# Lora_Basic_Gateway__Module_V1_0_20230419.net
KiCad netlist of a schematic drawn in EAGLE
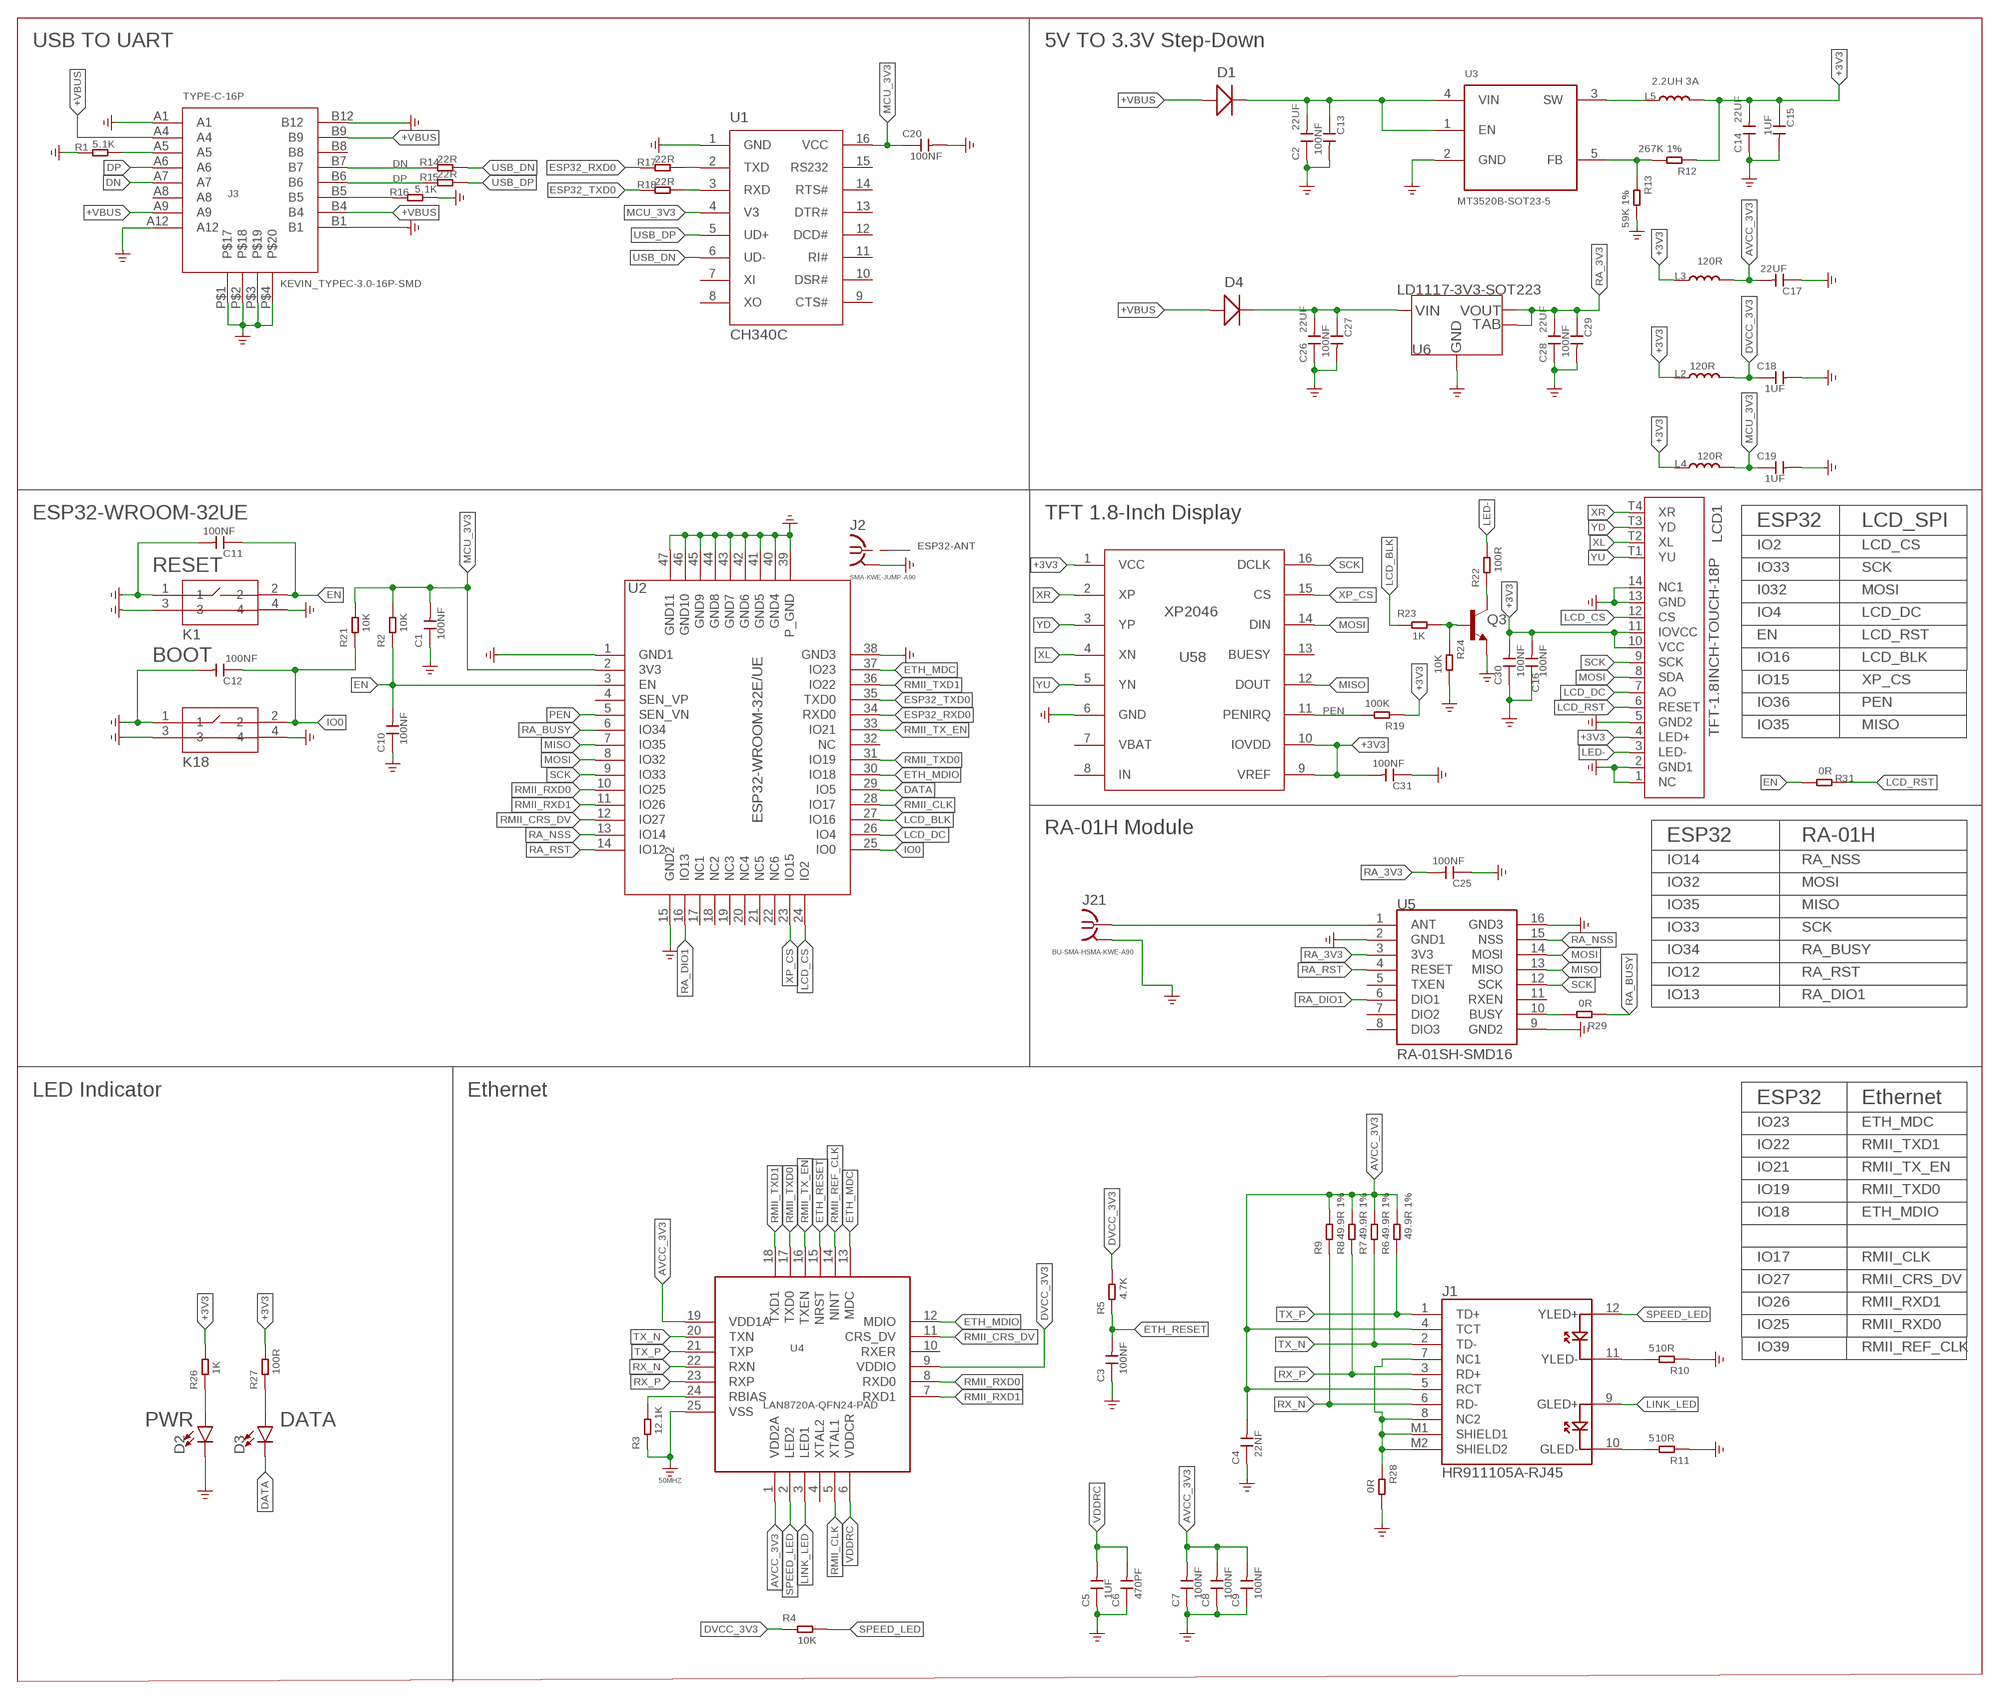
[diagram p0: schematic, sheet 1]

(export (version "E")
  (design (tool "Eeschema 10.0.6"))
  (components
    (comp (ref "C1")
      (value "100NF")
      (footprint "eagle-import:C0603")
      (libsource (lib "eagle-import") (part "C0603"))
    )
    (comp (ref "C2")
      (value "22UF")
      (footprint "eagle-import:C0805")
      (libsource (lib "eagle-import") (part "C0805"))
    )
    (comp (ref "C3")
      (value "100NF")
      (footprint "eagle-import:C0603")
      (libsource (lib "eagle-import") (part "C0603"))
    )
    (comp (ref "C4")
      (value "22NF")
      (footprint "eagle-import:C0603")
      (libsource (lib "eagle-import") (part "C0603"))
    )
    (comp (ref "C5")
      (value "1UF")
      (footprint "eagle-import:C0603")
      (libsource (lib "eagle-import") (part "C0603"))
    )
    (comp (ref "C6")
      (value "470PF")
      (footprint "eagle-import:C0603")
      (libsource (lib "eagle-import") (part "C0603"))
    )
    (comp (ref "C7")
      (value "100NF")
      (footprint "eagle-import:C0603")
      (libsource (lib "eagle-import") (part "C0603"))
    )
    (comp (ref "C8")
      (value "100NF")
      (footprint "eagle-import:C0603")
      (libsource (lib "eagle-import") (part "C0603"))
    )
    (comp (ref "C9")
      (value "100NF")
      (footprint "eagle-import:C0603")
      (libsource (lib "eagle-import") (part "C0603"))
    )
    (comp (ref "C10")
      (value "100NF")
      (footprint "eagle-import:C0603")
      (libsource (lib "eagle-import") (part "C0603"))
    )
    (comp (ref "C11")
      (value "100NF")
      (footprint "eagle-import:C0603")
      (libsource (lib "eagle-import") (part "C0603"))
    )
    (comp (ref "C12")
      (value "100NF")
      (footprint "eagle-import:C0603")
      (libsource (lib "eagle-import") (part "C0603"))
    )
    (comp (ref "C13")
      (value "100NF")
      (footprint "eagle-import:C0603")
      (libsource (lib "eagle-import") (part "C0603"))
    )
    (comp (ref "C14")
      (value "22UF")
      (footprint "eagle-import:C0805")
      (libsource (lib "eagle-import") (part "C0805"))
    )
    (comp (ref "C15")
      (value "1UF")
      (footprint "eagle-import:C0603")
      (libsource (lib "eagle-import") (part "C0603"))
    )
    (comp (ref "C16")
      (value "100NF")
      (footprint "eagle-import:C0603")
      (libsource (lib "eagle-import") (part "C0603"))
    )
    (comp (ref "C17")
      (value "22UF")
      (footprint "eagle-import:C0805")
      (libsource (lib "eagle-import") (part "C0805"))
    )
    (comp (ref "C18")
      (value "1UF")
      (footprint "eagle-import:C0603")
      (libsource (lib "eagle-import") (part "C0603"))
    )
    (comp (ref "C19")
      (value "1UF")
      (footprint "eagle-import:C0603")
      (libsource (lib "eagle-import") (part "C0603"))
    )
    (comp (ref "C20")
      (value "100NF")
      (footprint "eagle-import:C0603")
      (libsource (lib "eagle-import") (part "C0603"))
    )
    (comp (ref "C25")
      (value "100NF")
      (footprint "eagle-import:C0603")
      (libsource (lib "eagle-import") (part "C0603"))
    )
    (comp (ref "C26")
      (value "22UF")
      (footprint "eagle-import:C0805")
      (libsource (lib "eagle-import") (part "C0805"))
    )
    (comp (ref "C27")
      (value "100NF")
      (footprint "eagle-import:C0603")
      (libsource (lib "eagle-import") (part "C0603"))
    )
    (comp (ref "C28")
      (value "22UF")
      (footprint "eagle-import:C0805")
      (libsource (lib "eagle-import") (part "C0805"))
    )
    (comp (ref "C29")
      (value "100NF")
      (footprint "eagle-import:C0603")
      (libsource (lib "eagle-import") (part "C0603"))
    )
    (comp (ref "C30")
      (value "100NF")
      (footprint "eagle-import:C0603")
      (libsource (lib "eagle-import") (part "C0603"))
    )
    (comp (ref "C31")
      (value "100NF")
      (footprint "eagle-import:C0603")
      (libsource (lib "eagle-import") (part "C0603"))
    )
    (comp (ref "D1")
      (value "DIODEB130L-13-F")
      (footprint "eagle-import:SMA")
      (libsource (lib "eagle-import") (part "DIODEB130L-13-F"))
    )
    (comp (ref "D2")
      (value "LED")
      (footprint "eagle-import:LED-F3MM-DIP2-A90")
      (libsource (lib "eagle-import") (part "LED"))
    )
    (comp (ref "D3")
      (value "LED")
      (footprint "eagle-import:LED-F3MM-DIP2-A90")
      (libsource (lib "eagle-import") (part "LED"))
    )
    (comp (ref "D4")
      (value "DIODEB130L-13-F")
      (footprint "eagle-import:SMA")
      (libsource (lib "eagle-import") (part "DIODEB130L-13-F"))
    )
    (comp (ref "J1")
      (value "HR911105A-RJ45")
      (footprint "eagle-import:HR911105A-RJ45")
      (libsource (lib "eagle-import") (part "HR911105A-RJ45"))
    )
    (comp (ref "J2")
      (value "SMA-KWE-JUMP-A90")
      (footprint "eagle-import:SMA-KWE-JUMP-A90")
      (libsource (lib "eagle-import") (part "SMA-KWE-JUMP-A90"))
    )
    (comp (ref "J3")
      (value "KEVIN_TYPEC-3.0-16P-SMD")
      (footprint "eagle-import:KEVIN_3.0TYPEC-SMD")
      (libsource (lib "eagle-import") (part "KEVIN_TYPEC-3.0-16P-SMD"))
    )
    (comp (ref "J21")
      (value "BU-SMA-HSMA-KWE-A90")
      (footprint "eagle-import:SMA-KWE-A90")
      (libsource (lib "eagle-import") (part "BU-SMA-HSMA-KWE-A90"))
    )
    (comp (ref "K1")
      (value "KEY_666MM_DIPA90")
      (footprint "eagle-import:KEY_6_6_6MM_DIPA90")
      (libsource (lib "eagle-import") (part "KEY_666MM_DIPA90"))
    )
    (comp (ref "K18")
      (value "KEY_666MM_DIPA90")
      (footprint "eagle-import:KEY_6_6_6MM_DIPA90")
      (libsource (lib "eagle-import") (part "KEY_666MM_DIPA90"))
    )
    (comp (ref "L2")
      (value "120R")
      (footprint "eagle-import:L0805")
      (libsource (lib "eagle-import") (part "L0805"))
    )
    (comp (ref "L3")
      (value "120R")
      (footprint "eagle-import:L0603")
      (libsource (lib "eagle-import") (part "L0603"))
    )
    (comp (ref "L4")
      (value "120R")
      (footprint "eagle-import:L0805")
      (libsource (lib "eagle-import") (part "L0805"))
    )
    (comp (ref "L5")
      (value "2.2UH 3A")
      (footprint "eagle-import:L0420")
      (libsource (lib "eagle-import") (part "L"))
    )
    (comp (ref "LCD1")
      (value "TFT-1.8INCH-TOUCH-18P")
      (footprint "eagle-import:TFT-1.8INCH-TOUCH-18P-SMD")
      (libsource (lib "eagle-import") (part "TFT-1.8INCH-TOUCH-18P"))
    )
    (comp (ref "Q3")
      (value "600mA/40V")
      (footprint "eagle-import:SOT23-3")
      (libsource (lib "eagle-import") (part "TRANS_NPN-MMBT2222AL"))
    )
    (comp (ref "R1")
      (value "5.1K")
      (footprint "eagle-import:R0603")
      (libsource (lib "eagle-import") (part "R0603"))
    )
    (comp (ref "R2")
      (value "10K")
      (footprint "eagle-import:R0603")
      (libsource (lib "eagle-import") (part "R0603"))
    )
    (comp (ref "R3")
      (value "12.1K")
      (footprint "eagle-import:R0603")
      (libsource (lib "eagle-import") (part "R0603"))
    )
    (comp (ref "R4")
      (value "10K")
      (footprint "eagle-import:R0603")
      (libsource (lib "eagle-import") (part "R0603"))
    )
    (comp (ref "R5")
      (value "4.7K")
      (footprint "eagle-import:R0603")
      (libsource (lib "eagle-import") (part "R0603"))
    )
    (comp (ref "R6")
      (value "49.9R 1%")
      (footprint "eagle-import:R0603")
      (libsource (lib "eagle-import") (part "R0603"))
    )
    (comp (ref "R7")
      (value "49.9R 1%")
      (footprint "eagle-import:R0603")
      (libsource (lib "eagle-import") (part "R0603"))
    )
    (comp (ref "R8")
      (value "49.9R 1%")
      (footprint "eagle-import:R0603")
      (libsource (lib "eagle-import") (part "R0603"))
    )
    (comp (ref "R9")
      (value "49.9R 1%")
      (footprint "eagle-import:R0603")
      (libsource (lib "eagle-import") (part "R0603"))
    )
    (comp (ref "R10")
      (value "510R")
      (footprint "eagle-import:R0603")
      (libsource (lib "eagle-import") (part "R0603"))
    )
    (comp (ref "R11")
      (value "510R")
      (footprint "eagle-import:R0603")
      (libsource (lib "eagle-import") (part "R0603"))
    )
    (comp (ref "R12")
      (value "267K 1%")
      (footprint "eagle-import:R0603")
      (libsource (lib "eagle-import") (part "R0603"))
    )
    (comp (ref "R13")
      (value "59K 1%")
      (footprint "eagle-import:R0603")
      (libsource (lib "eagle-import") (part "R0603"))
    )
    (comp (ref "R14")
      (value "22R")
      (footprint "eagle-import:R0603")
      (libsource (lib "eagle-import") (part "R0603"))
    )
    (comp (ref "R15")
      (value "22R")
      (footprint "eagle-import:R0603")
      (libsource (lib "eagle-import") (part "R0603"))
    )
    (comp (ref "R16")
      (value "5.1K")
      (footprint "eagle-import:R0603")
      (libsource (lib "eagle-import") (part "R0603"))
    )
    (comp (ref "R17")
      (value "22R")
      (footprint "eagle-import:R0603")
      (libsource (lib "eagle-import") (part "R0603"))
    )
    (comp (ref "R18")
      (value "22R")
      (footprint "eagle-import:R0603")
      (libsource (lib "eagle-import") (part "R0603"))
    )
    (comp (ref "R19")
      (value "100K")
      (footprint "eagle-import:R0603")
      (libsource (lib "eagle-import") (part "R0603"))
    )
    (comp (ref "R21")
      (value "10K")
      (footprint "eagle-import:R0603")
      (libsource (lib "eagle-import") (part "R0603"))
    )
    (comp (ref "R22")
      (value "100R")
      (footprint "eagle-import:R0603")
      (libsource (lib "eagle-import") (part "R0603"))
    )
    (comp (ref "R23")
      (value "1K")
      (footprint "eagle-import:R0603")
      (libsource (lib "eagle-import") (part "R0603"))
    )
    (comp (ref "R24")
      (value "10K")
      (footprint "eagle-import:R0603")
      (libsource (lib "eagle-import") (part "R0603"))
    )
    (comp (ref "R26")
      (value "1K")
      (footprint "eagle-import:R0603")
      (libsource (lib "eagle-import") (part "R0603"))
    )
    (comp (ref "R27")
      (value "100R")
      (footprint "eagle-import:R0603")
      (libsource (lib "eagle-import") (part "R0603"))
    )
    (comp (ref "R28")
      (value "0R")
      (footprint "eagle-import:R0603")
      (libsource (lib "eagle-import") (part "R0603"))
    )
    (comp (ref "R29")
      (value "0R")
      (footprint "eagle-import:R0603")
      (libsource (lib "eagle-import") (part "R0603"))
    )
    (comp (ref "R31")
      (value "0R")
      (footprint "eagle-import:R0603")
      (libsource (lib "eagle-import") (part "R0603"))
    )
    (comp (ref "U1")
      (value "CH340C")
      (footprint "eagle-import:SOP-16")
      (libsource (lib "eagle-import") (part "CH340G"))
    )
    (comp (ref "U2")
      (value "ESP32-WROOM-32E/UE")
      (footprint "eagle-import:ESP32-WROOM-32UE")
      (libsource (lib "eagle-import") (part "ESP32-WROOM-32E/UE"))
    )
    (comp (ref "U3")
      (value "MT3520B-SOT23-5")
      (footprint "eagle-import:IC_SOT23-5")
      (libsource (lib "eagle-import") (part "HM3420B"))
    )
    (comp (ref "U4")
      (value "LAN8720A-QFN24-PAD")
      (footprint "eagle-import:QFN24-PAD")
      (libsource (lib "eagle-import") (part "LAN8720A-QFN24-PAD"))
    )
    (comp (ref "U5")
      (value "RA-01SH-SMD16")
      (footprint "eagle-import:RA-01SH-SMD16")
      (libsource (lib "eagle-import") (part "RA-01SH-SMD16"))
    )
    (comp (ref "U6")
      (value "LD1117-3V3-SOT223")
      (footprint "eagle-import:SOT223")
      (libsource (lib "eagle-import") (part "LD1117-3V3-SOT223"))
    )
    (comp (ref "U58")
      (value "XP2046")
      (footprint "eagle-import:XP2046-SSOP16")
      (libsource (lib "eagle-import") (part "XP2046"))
    )
  )
  (nets
    (net (code "1") (name "+3V3") (class "Default")
      (node (ref "C14") (pin "2") (pinfunction "2_2") (pintype "passive"))
      (node (ref "C15") (pin "1") (pinfunction "1_1") (pintype "passive"))
      (node (ref "C16") (pin "2") (pinfunction "2_2") (pintype "passive"))
      (node (ref "C30") (pin "2") (pinfunction "2_2") (pintype "passive"))
      (node (ref "C31") (pin "2") (pinfunction "2_2") (pintype "passive"))
      (node (ref "L2") (pin "1") (pinfunction "1_1") (pintype "passive"))
      (node (ref "L3") (pin "1") (pinfunction "1_1") (pintype "passive"))
      (node (ref "L4") (pin "1") (pinfunction "1_1") (pintype "passive"))
      (node (ref "L5") (pin "2") (pinfunction "2_2") (pintype "passive"))
      (node (ref "LCD1") (pin "10") (pinfunction "VCC_10") (pintype "bidirectional"))
      (node (ref "LCD1") (pin "11") (pinfunction "IOVCC_11") (pintype "bidirectional"))
      (node (ref "LCD1") (pin "4") (pinfunction "LED+_4") (pintype "bidirectional"))
      (node (ref "R12") (pin "1") (pinfunction "1_1") (pintype "passive"))
      (node (ref "R19") (pin "1") (pinfunction "1_1") (pintype "passive"))
      (node (ref "R26") (pin "2") (pinfunction "2_2") (pintype "passive"))
      (node (ref "R27") (pin "2") (pinfunction "2_2") (pintype "passive"))
      (node (ref "U58") (pin "1") (pinfunction "VCC_1") (pintype "bidirectional"))
      (node (ref "U58") (pin "10") (pinfunction "IOVDD_10") (pintype "bidirectional"))
      (node (ref "U58") (pin "9") (pinfunction "VREF_9") (pintype "bidirectional"))
    )
    (net (code "2") (name "+VBUS") (class "Default")
      (node (ref "D1") (pin "2") (pinfunction "+_2") (pintype "passive"))
      (node (ref "D4") (pin "2") (pinfunction "+_2") (pintype "passive"))
      (node (ref "J3") (pin "A4") (pinfunction "A4_A4") (pintype "bidirectional"))
      (node (ref "J3") (pin "A9") (pinfunction "A9_A9") (pintype "bidirectional"))
      (node (ref "J3") (pin "B4") (pinfunction "B4_B4") (pintype "bidirectional"))
      (node (ref "J3") (pin "B9") (pinfunction "B9_B9") (pintype "bidirectional"))
    )
    (net (code "3") (name "50MHZ") (class "Default")
      (node (ref "C1") (pin "1") (pinfunction "1_1") (pintype "passive"))
      (node (ref "C10") (pin "1") (pinfunction "1_1") (pintype "passive"))
      (node (ref "C11") (pin "2") (pinfunction "2_2") (pintype "passive"))
      (node (ref "C12") (pin "2") (pinfunction "2_2") (pintype "passive"))
      (node (ref "C13") (pin "2") (pinfunction "2_2") (pintype "passive"))
      (node (ref "C14") (pin "1") (pinfunction "1_1") (pintype "passive"))
      (node (ref "C15") (pin "2") (pinfunction "2_2") (pintype "passive"))
      (node (ref "C16") (pin "1") (pinfunction "1_1") (pintype "passive"))
      (node (ref "C17") (pin "1") (pinfunction "1_1") (pintype "passive"))
      (node (ref "C18") (pin "2") (pinfunction "2_2") (pintype "passive"))
      (node (ref "C19") (pin "2") (pinfunction "2_2") (pintype "passive"))
      (node (ref "C2") (pin "1") (pinfunction "1_1") (pintype "passive"))
      (node (ref "C20") (pin "2") (pinfunction "2_2") (pintype "passive"))
      (node (ref "C25") (pin "1") (pinfunction "1_1") (pintype "passive"))
      (node (ref "C26") (pin "1") (pinfunction "1_1") (pintype "passive"))
      (node (ref "C27") (pin "2") (pinfunction "2_2") (pintype "passive"))
      (node (ref "C28") (pin "1") (pinfunction "1_1") (pintype "passive"))
      (node (ref "C29") (pin "2") (pinfunction "2_2") (pintype "passive"))
      (node (ref "C3") (pin "1") (pinfunction "1_1") (pintype "passive"))
      (node (ref "C30") (pin "1") (pinfunction "1_1") (pintype "passive"))
      (node (ref "C31") (pin "1") (pinfunction "1_1") (pintype "passive"))
      (node (ref "C4") (pin "1") (pinfunction "1_1") (pintype "passive"))
      (node (ref "C5") (pin "1") (pinfunction "1_1") (pintype "passive"))
      (node (ref "C6") (pin "1") (pinfunction "1_1") (pintype "passive"))
      (node (ref "C7") (pin "1") (pinfunction "1_1") (pintype "passive"))
      (node (ref "C8") (pin "1") (pinfunction "1_1") (pintype "passive"))
      (node (ref "C9") (pin "1") (pinfunction "1_1") (pintype "passive"))
      (node (ref "D2") (pin "K") (pinfunction "C_K") (pintype "passive"))
      (node (ref "J2") (pin "2") (pinfunction "2_2") (pintype "passive"))
      (node (ref "J2") (pin "3") (pinfunction "2_3") (pintype "passive"))
      (node (ref "J2") (pin "4") (pinfunction "2_4") (pintype "passive"))
      (node (ref "J2") (pin "5") (pinfunction "2_5") (pintype "passive"))
      (node (ref "J21") (pin "2") (pinfunction "2_2") (pintype "passive"))
      (node (ref "J21") (pin "3") (pinfunction "2_3") (pintype "passive"))
      (node (ref "J21") (pin "4") (pinfunction "2_4") (pintype "passive"))
      (node (ref "J21") (pin "5") (pinfunction "2_5") (pintype "passive"))
      (node (ref "J3") (pin "A1") (pinfunction "A1_A1") (pintype "bidirectional"))
      (node (ref "J3") (pin "A12") (pinfunction "A12_A12") (pintype "bidirectional"))
      (node (ref "J3") (pin "B1") (pinfunction "B1_B1") (pintype "bidirectional"))
      (node (ref "J3") (pin "B12") (pinfunction "B12_B12") (pintype "bidirectional"))
      (node (ref "J3") (pin "P$1") (pinfunction "P$17_P$1") (pintype "bidirectional"))
      (node (ref "J3") (pin "P$2") (pinfunction "P$18_P$2") (pintype "bidirectional"))
      (node (ref "J3") (pin "P$3") (pinfunction "P$19_P$3") (pintype "bidirectional"))
      (node (ref "J3") (pin "P$4") (pinfunction "P$20_P$4") (pintype "bidirectional"))
      (node (ref "K1") (pin "1") (pinfunction "1_1") (pintype "bidirectional"))
      (node (ref "K1") (pin "3") (pinfunction "3_3") (pintype "bidirectional"))
      (node (ref "K1") (pin "4") (pinfunction "4_4") (pintype "bidirectional"))
      (node (ref "K18") (pin "1") (pinfunction "1_1") (pintype "bidirectional"))
      (node (ref "K18") (pin "3") (pinfunction "3_3") (pintype "bidirectional"))
      (node (ref "K18") (pin "4") (pinfunction "4_4") (pintype "bidirectional"))
      (node (ref "LCD1") (pin "1") (pinfunction "NC_1") (pintype "bidirectional"))
      (node (ref "LCD1") (pin "13") (pinfunction "GND_13") (pintype "bidirectional"))
      (node (ref "LCD1") (pin "14") (pinfunction "NC1_14") (pintype "bidirectional"))
      (node (ref "LCD1") (pin "2") (pinfunction "GND1_2") (pintype "bidirectional"))
      (node (ref "LCD1") (pin "5") (pinfunction "GND2_5") (pintype "bidirectional"))
      (node (ref "Q3") (pin "2") (pinfunction "E_2") (pintype "passive"))
      (node (ref "R1") (pin "1") (pinfunction "1_1") (pintype "passive"))
      (node (ref "R10") (pin "1") (pinfunction "1_1") (pintype "passive"))
      (node (ref "R11") (pin "1") (pinfunction "1_1") (pintype "passive"))
      (node (ref "R13") (pin "2") (pinfunction "2_2") (pintype "passive"))
      (node (ref "R16") (pin "2") (pinfunction "2_2") (pintype "passive"))
      (node (ref "R24") (pin "2") (pinfunction "2_2") (pintype "passive"))
      (node (ref "R28") (pin "2") (pinfunction "2_2") (pintype "passive"))
      (node (ref "R3") (pin "1") (pinfunction "1_1") (pintype "passive"))
      (node (ref "U1") (pin "1") (pinfunction "GND_1") (pintype "bidirectional"))
      (node (ref "U2") (pin "1") (pinfunction "GND1_1") (pintype "bidirectional"))
      (node (ref "U2") (pin "15") (pinfunction "GND2_15") (pintype "bidirectional"))
      (node (ref "U2") (pin "38") (pinfunction "GND3_38") (pintype "bidirectional"))
      (node (ref "U2") (pin "39") (pinfunction "P_GND_39") (pintype "bidirectional"))
      (node (ref "U2") (pin "40") (pinfunction "GND4_40") (pintype "bidirectional"))
      (node (ref "U2") (pin "41") (pinfunction "GND5_41") (pintype "bidirectional"))
      (node (ref "U2") (pin "42") (pinfunction "GND6_42") (pintype "bidirectional"))
      (node (ref "U2") (pin "43") (pinfunction "GND7_43") (pintype "bidirectional"))
      (node (ref "U2") (pin "44") (pinfunction "GND8_44") (pintype "bidirectional"))
      (node (ref "U2") (pin "45") (pinfunction "GND9_45") (pintype "bidirectional"))
      (node (ref "U2") (pin "46") (pinfunction "GND10_46") (pintype "bidirectional"))
      (node (ref "U2") (pin "47") (pinfunction "GND11_47") (pintype "bidirectional"))
      (node (ref "U3") (pin "2") (pinfunction "GND_2") (pintype "bidirectional"))
      (node (ref "U4") (pin "25") (pinfunction "VSS_25") (pintype "bidirectional"))
      (node (ref "U5") (pin "16") (pinfunction "GND3_16") (pintype "bidirectional"))
      (node (ref "U5") (pin "2") (pinfunction "GND1_2") (pintype "bidirectional"))
      (node (ref "U5") (pin "9") (pinfunction "GND2_9") (pintype "bidirectional"))
      (node (ref "U58") (pin "6") (pinfunction "GND_6") (pintype "bidirectional"))
      (node (ref "U6") (pin "1") (pinfunction "GND_1") (pintype "bidirectional"))
    )
    (net (code "4") (name "AVCC_3V3") (class "Default")
      (node (ref "C17") (pin "2") (pinfunction "2_2") (pintype "passive"))
      (node (ref "C4") (pin "2") (pinfunction "2_2") (pintype "passive"))
      (node (ref "C7") (pin "2") (pinfunction "2_2") (pintype "passive"))
      (node (ref "C8") (pin "2") (pinfunction "2_2") (pintype "passive"))
      (node (ref "C9") (pin "2") (pinfunction "2_2") (pintype "passive"))
      (node (ref "J1") (pin "4") (pinfunction "TCT_4") (pintype "bidirectional"))
      (node (ref "J1") (pin "5") (pinfunction "RCT_5") (pintype "bidirectional"))
      (node (ref "L3") (pin "2") (pinfunction "2_2") (pintype "passive"))
      (node (ref "R6") (pin "2") (pinfunction "2_2") (pintype "passive"))
      (node (ref "R7") (pin "2") (pinfunction "2_2") (pintype "passive"))
      (node (ref "R8") (pin "2") (pinfunction "2_2") (pintype "passive"))
      (node (ref "R9") (pin "2") (pinfunction "2_2") (pintype "passive"))
      (node (ref "U4") (pin "1") (pinfunction "VDD2A_1") (pintype "bidirectional"))
      (node (ref "U4") (pin "19") (pinfunction "VDD1A_19") (pintype "bidirectional"))
    )
    (net (code "5") (name "DATA") (class "Default")
      (node (ref "D3") (pin "K") (pinfunction "C_K") (pintype "passive"))
      (node (ref "U2") (pin "29") (pinfunction "IO5_29") (pintype "bidirectional"))
    )
    (net (code "6") (name "DN") (class "Default")
      (node (ref "J3") (pin "A7") (pinfunction "A7_A7") (pintype "bidirectional"))
      (node (ref "J3") (pin "B7") (pinfunction "B7_B7") (pintype "bidirectional"))
      (node (ref "R14") (pin "1") (pinfunction "1_1") (pintype "passive"))
    )
    (net (code "7") (name "DP") (class "Default")
      (node (ref "J3") (pin "A6") (pinfunction "A6_A6") (pintype "bidirectional"))
      (node (ref "J3") (pin "B6") (pinfunction "B6_B6") (pintype "bidirectional"))
      (node (ref "R15") (pin "1") (pinfunction "1_1") (pintype "passive"))
    )
    (net (code "8") (name "DVCC_3V3") (class "Default")
      (node (ref "C18") (pin "1") (pinfunction "1_1") (pintype "passive"))
      (node (ref "L2") (pin "2") (pinfunction "2_2") (pintype "passive"))
      (node (ref "R4") (pin "1") (pinfunction "1_1") (pintype "passive"))
      (node (ref "R5") (pin "2") (pinfunction "2_2") (pintype "passive"))
      (node (ref "U4") (pin "9") (pinfunction "VDDIO_9") (pintype "bidirectional"))
    )
    (net (code "9") (name "EN") (class "Default")
      (node (ref "C10") (pin "2") (pinfunction "2_2") (pintype "passive"))
      (node (ref "C11") (pin "1") (pinfunction "1_1") (pintype "passive"))
      (node (ref "K1") (pin "2") (pinfunction "2_2") (pintype "bidirectional"))
      (node (ref "R2") (pin "1") (pinfunction "1_1") (pintype "passive"))
      (node (ref "R31") (pin "2") (pinfunction "2_2") (pintype "passive"))
      (node (ref "U2") (pin "3") (pinfunction "EN_3") (pintype "bidirectional"))
    )
    (net (code "10") (name "ESP32_RXD0") (class "Default")
      (node (ref "R17") (pin "1") (pinfunction "1_1") (pintype "passive"))
      (node (ref "U2") (pin "34") (pinfunction "RXD0_34") (pintype "bidirectional"))
    )
    (net (code "11") (name "ESP32_TXD0") (class "Default")
      (node (ref "R18") (pin "1") (pinfunction "1_1") (pintype "passive"))
      (node (ref "U2") (pin "35") (pinfunction "TXD0_35") (pintype "bidirectional"))
    )
    (net (code "12") (name "ETH_MDC") (class "Default")
      (node (ref "U2") (pin "37") (pinfunction "IO23_37") (pintype "bidirectional"))
      (node (ref "U4") (pin "13") (pinfunction "MDC_13") (pintype "bidirectional"))
    )
    (net (code "13") (name "ETH_MDIO") (class "Default")
      (node (ref "U2") (pin "30") (pinfunction "IO18_30") (pintype "bidirectional"))
      (node (ref "U4") (pin "12") (pinfunction "MDIO_12") (pintype "bidirectional"))
    )
    (net (code "14") (name "ETH_RESET") (class "Default")
      (node (ref "C3") (pin "2") (pinfunction "2_2") (pintype "passive"))
      (node (ref "R5") (pin "1") (pinfunction "1_1") (pintype "passive"))
      (node (ref "U4") (pin "15") (pinfunction "NRST_15") (pintype "bidirectional"))
    )
    (net (code "15") (name "IO0") (class "Default")
      (node (ref "C12") (pin "1") (pinfunction "1_1") (pintype "passive"))
      (node (ref "K18") (pin "2") (pinfunction "2_2") (pintype "bidirectional"))
      (node (ref "R21") (pin "1") (pinfunction "1_1") (pintype "passive"))
      (node (ref "U2") (pin "25") (pinfunction "IO0_25") (pintype "bidirectional"))
    )
    (net (code "16") (name "LCD_BLK") (class "Default")
      (node (ref "R23") (pin "1") (pinfunction "1_1") (pintype "passive"))
      (node (ref "U2") (pin "27") (pinfunction "IO16_27") (pintype "bidirectional"))
    )
    (net (code "17") (name "LCD_CS") (class "Default")
      (node (ref "LCD1") (pin "12") (pinfunction "CS_12") (pintype "bidirectional"))
      (node (ref "U2") (pin "24") (pinfunction "IO2_24") (pintype "bidirectional"))
    )
    (net (code "18") (name "LCD_DC") (class "Default")
      (node (ref "LCD1") (pin "7") (pinfunction "AO_7") (pintype "bidirectional"))
      (node (ref "U2") (pin "26") (pinfunction "IO4_26") (pintype "bidirectional"))
    )
    (net (code "19") (name "LCD_RST") (class "Default")
      (node (ref "LCD1") (pin "6") (pinfunction "RESET_6") (pintype "bidirectional"))
      (node (ref "R31") (pin "1") (pinfunction "1_1") (pintype "passive"))
    )
    (net (code "20") (name "LED-") (class "Default")
      (node (ref "LCD1") (pin "3") (pinfunction "LED-_3") (pintype "bidirectional"))
      (node (ref "R22") (pin "2") (pinfunction "2_2") (pintype "passive"))
    )
    (net (code "21") (name "LINK_LED") (class "Default")
      (node (ref "J1") (pin "9") (pinfunction "GLED+_9") (pintype "bidirectional"))
      (node (ref "U4") (pin "3") (pinfunction "LED1_3") (pintype "bidirectional"))
    )
    (net (code "22") (name "MCU_3V3") (class "Default")
      (node (ref "C1") (pin "2") (pinfunction "2_2") (pintype "passive"))
      (node (ref "C19") (pin "1") (pinfunction "1_1") (pintype "passive"))
      (node (ref "C20") (pin "1") (pinfunction "1_1") (pintype "passive"))
      (node (ref "L4") (pin "2") (pinfunction "2_2") (pintype "passive"))
      (node (ref "R2") (pin "2") (pinfunction "2_2") (pintype "passive"))
      (node (ref "R21") (pin "2") (pinfunction "2_2") (pintype "passive"))
      (node (ref "U1") (pin "16") (pinfunction "VCC_16") (pintype "bidirectional"))
      (node (ref "U1") (pin "4") (pinfunction "V3_4") (pintype "bidirectional"))
      (node (ref "U2") (pin "2") (pinfunction "3V3_2") (pintype "bidirectional"))
    )
    (net (code "23") (name "MISO") (class "Default")
      (node (ref "U2") (pin "7") (pinfunction "IO35_7") (pintype "bidirectional"))
      (node (ref "U5") (pin "13") (pinfunction "MISO_13") (pintype "bidirectional"))
      (node (ref "U58") (pin "12") (pinfunction "DOUT_12") (pintype "bidirectional"))
    )
    (net (code "24") (name "MOSI") (class "Default")
      (node (ref "LCD1") (pin "8") (pinfunction "SDA_8") (pintype "bidirectional"))
      (node (ref "U2") (pin "8") (pinfunction "IO32_8") (pintype "bidirectional"))
      (node (ref "U5") (pin "14") (pinfunction "MOSI_14") (pintype "bidirectional"))
      (node (ref "U58") (pin "14") (pinfunction "DIN_14") (pintype "bidirectional"))
    )
    (net (code "25") (name "Net-(D1--)") (class "Default")
      (node (ref "C13") (pin "1") (pinfunction "1_1") (pintype "passive"))
      (node (ref "C2") (pin "2") (pinfunction "2_2") (pintype "passive"))
      (node (ref "D1") (pin "1") (pinfunction "-_1") (pintype "passive"))
      (node (ref "U3") (pin "1") (pinfunction "EN_1") (pintype "bidirectional"))
      (node (ref "U3") (pin "4") (pinfunction "VIN_4") (pintype "bidirectional"))
    )
    (net (code "26") (name "Net-(D2-PadA)") (class "Default")
      (node (ref "D2") (pin "A") (pinfunction "A_A") (pintype "passive"))
      (node (ref "R26") (pin "1") (pinfunction "1_1") (pintype "passive"))
    )
    (net (code "27") (name "Net-(D3-PadA)") (class "Default")
      (node (ref "D3") (pin "A") (pinfunction "A_A") (pintype "passive"))
      (node (ref "R27") (pin "1") (pinfunction "1_1") (pintype "passive"))
    )
    (net (code "28") (name "Net-(D4--)") (class "Default")
      (node (ref "C26") (pin "2") (pinfunction "2_2") (pintype "passive"))
      (node (ref "C27") (pin "1") (pinfunction "1_1") (pintype "passive"))
      (node (ref "D4") (pin "1") (pinfunction "-_1") (pintype "passive"))
      (node (ref "U6") (pin "3") (pinfunction "VIN_3") (pintype "bidirectional"))
    )
    (net (code "29") (name "Net-(J1-GLED-)") (class "Default")
      (node (ref "J1") (pin "10") (pinfunction "GLED-_10") (pintype "bidirectional"))
      (node (ref "R11") (pin "2") (pinfunction "2_2") (pintype "passive"))
    )
    (net (code "30") (name "Net-(J1-NC1)") (class "Default")
      (node (ref "J1") (pin "7") (pinfunction "NC1_7") (pintype "bidirectional"))
      (node (ref "J1") (pin "8") (pinfunction "NC2_8") (pintype "bidirectional"))
      (node (ref "J1") (pin "M1") (pinfunction "SHIELD1_M1") (pintype "bidirectional"))
      (node (ref "J1") (pin "M2") (pinfunction "SHIELD2_M2") (pintype "bidirectional"))
      (node (ref "R28") (pin "1") (pinfunction "1_1") (pintype "passive"))
    )
    (net (code "31") (name "Net-(J1-YLED-)") (class "Default")
      (node (ref "J1") (pin "11") (pinfunction "YLED-_11") (pintype "bidirectional"))
      (node (ref "R10") (pin "2") (pinfunction "2_2") (pintype "passive"))
    )
    (net (code "32") (name "Net-(J3-PadA5)") (class "Default")
      (node (ref "J3") (pin "A5") (pinfunction "A5_A5") (pintype "bidirectional"))
      (node (ref "R1") (pin "2") (pinfunction "2_2") (pintype "passive"))
    )
    (net (code "33") (name "Net-(J3-PadB5)") (class "Default")
      (node (ref "J3") (pin "B5") (pinfunction "B5_B5") (pintype "bidirectional"))
      (node (ref "R16") (pin "1") (pinfunction "1_1") (pintype "passive"))
    )
    (net (code "34") (name "Net-(Q3-B)") (class "Default")
      (node (ref "Q3") (pin "1") (pinfunction "B_1") (pintype "passive"))
      (node (ref "R23") (pin "2") (pinfunction "2_2") (pintype "passive"))
      (node (ref "R24") (pin "1") (pinfunction "1_1") (pintype "passive"))
    )
    (net (code "35") (name "Net-(Q3-C)") (class "Default")
      (node (ref "Q3") (pin "3") (pinfunction "C_3") (pintype "passive"))
      (node (ref "R22") (pin "1") (pinfunction "1_1") (pintype "passive"))
    )
    (net (code "36") (name "Net-(U1-RXD)") (class "Default")
      (node (ref "R18") (pin "2") (pinfunction "2_2") (pintype "passive"))
      (node (ref "U1") (pin "3") (pinfunction "RXD_3") (pintype "bidirectional"))
    )
    (net (code "37") (name "Net-(U1-TXD)") (class "Default")
      (node (ref "R17") (pin "2") (pinfunction "2_2") (pintype "passive"))
      (node (ref "U1") (pin "2") (pinfunction "TXD_2") (pintype "bidirectional"))
    )
    (net (code "38") (name "Net-(U3-FB)") (class "Default")
      (node (ref "R12") (pin "2") (pinfunction "2_2") (pintype "passive"))
      (node (ref "R13") (pin "1") (pinfunction "1_1") (pintype "passive"))
      (node (ref "U3") (pin "5") (pinfunction "FB_5") (pintype "bidirectional"))
    )
    (net (code "39") (name "Net-(U3-SW)") (class "Default")
      (node (ref "L5") (pin "1") (pinfunction "1_1") (pintype "passive"))
      (node (ref "U3") (pin "3") (pinfunction "SW_3") (pintype "bidirectional"))
    )
    (net (code "40") (name "Net-(U4-RBIAS)") (class "Default")
      (node (ref "R3") (pin "2") (pinfunction "2_2") (pintype "passive"))
      (node (ref "U4") (pin "24") (pinfunction "RBIAS_24") (pintype "bidirectional"))
    )
    (net (code "41") (name "Net-(U5-ANT)") (class "Default")
      (node (ref "J21") (pin "1") (pinfunction "1_1") (pintype "passive"))
      (node (ref "U5") (pin "1") (pinfunction "ANT_1") (pintype "bidirectional"))
    )
    (net (code "42") (name "Net-(U5-BUSY)") (class "Default")
      (node (ref "R29") (pin "2") (pinfunction "2_2") (pintype "passive"))
      (node (ref "U5") (pin "10") (pinfunction "BUSY_10") (pintype "bidirectional"))
    )
    (net (code "43") (name "PEN") (class "Default")
      (node (ref "R19") (pin "2") (pinfunction "2_2") (pintype "passive"))
      (node (ref "U2") (pin "5") (pinfunction "SEN_VN_5") (pintype "bidirectional"))
      (node (ref "U58") (pin "11") (pinfunction "PENIRQ_11") (pintype "bidirectional"))
    )
    (net (code "44") (name "RA_3V3") (class "Default")
      (node (ref "C25") (pin "2") (pinfunction "2_2") (pintype "passive"))
      (node (ref "C28") (pin "2") (pinfunction "2_2") (pintype "passive"))
      (node (ref "C29") (pin "1") (pinfunction "1_1") (pintype "passive"))
      (node (ref "U5") (pin "3") (pinfunction "3V3_3") (pintype "bidirectional"))
      (node (ref "U6") (pin "2") (pinfunction "VOUT_2") (pintype "bidirectional"))
      (node (ref "U6") (pin "4") (pinfunction "TAB_4") (pintype "bidirectional"))
    )
    (net (code "45") (name "RA_BUSY") (class "Default")
      (node (ref "R29") (pin "1") (pinfunction "1_1") (pintype "passive"))
      (node (ref "U2") (pin "6") (pinfunction "IO34_6") (pintype "bidirectional"))
    )
    (net (code "46") (name "RA_DIO1") (class "Default")
      (node (ref "U2") (pin "16") (pinfunction "IO13_16") (pintype "bidirectional"))
      (node (ref "U5") (pin "6") (pinfunction "DIO1_6") (pintype "bidirectional"))
    )
    (net (code "47") (name "RA_NSS") (class "Default")
      (node (ref "U2") (pin "13") (pinfunction "IO14_13") (pintype "bidirectional"))
      (node (ref "U5") (pin "15") (pinfunction "NSS_15") (pintype "bidirectional"))
    )
    (net (code "48") (name "RA_RST") (class "Default")
      (node (ref "U2") (pin "14") (pinfunction "IO12_14") (pintype "bidirectional"))
      (node (ref "U5") (pin "4") (pinfunction "RESET_4") (pintype "bidirectional"))
    )
    (net (code "49") (name "RMII_CLK") (class "Default")
      (node (ref "U2") (pin "28") (pinfunction "IO17_28") (pintype "bidirectional"))
      (node (ref "U4") (pin "5") (pinfunction "XTAL1_5") (pintype "bidirectional"))
    )
    (net (code "50") (name "RMII_CRS_DV") (class "Default")
      (node (ref "U2") (pin "12") (pinfunction "IO27_12") (pintype "bidirectional"))
      (node (ref "U4") (pin "11") (pinfunction "CRS_DV_11") (pintype "bidirectional"))
    )
    (net (code "51") (name "RMII_REF_CLK") (class "Default")
      (node (ref "U4") (pin "14") (pinfunction "NINT_14") (pintype "bidirectional"))
    )
    (net (code "52") (name "RMII_RXD0") (class "Default")
      (node (ref "U2") (pin "10") (pinfunction "IO25_10") (pintype "bidirectional"))
      (node (ref "U4") (pin "8") (pinfunction "RXD0_8") (pintype "bidirectional"))
    )
    (net (code "53") (name "RMII_RXD1") (class "Default")
      (node (ref "U2") (pin "11") (pinfunction "IO26_11") (pintype "bidirectional"))
      (node (ref "U4") (pin "7") (pinfunction "RXD1_7") (pintype "bidirectional"))
    )
    (net (code "54") (name "RMII_TXD0") (class "Default")
      (node (ref "U2") (pin "31") (pinfunction "IO19_31") (pintype "bidirectional"))
      (node (ref "U4") (pin "17") (pinfunction "TXD0_17") (pintype "bidirectional"))
    )
    (net (code "55") (name "RMII_TXD1") (class "Default")
      (node (ref "U2") (pin "36") (pinfunction "IO22_36") (pintype "bidirectional"))
      (node (ref "U4") (pin "18") (pinfunction "TXD1_18") (pintype "bidirectional"))
    )
    (net (code "56") (name "RMII_TX_EN") (class "Default")
      (node (ref "U2") (pin "33") (pinfunction "IO21_33") (pintype "bidirectional"))
      (node (ref "U4") (pin "16") (pinfunction "TXEN_16") (pintype "bidirectional"))
    )
    (net (code "57") (name "RX_N") (class "Default")
      (node (ref "J1") (pin "6") (pinfunction "RD-_6") (pintype "bidirectional"))
      (node (ref "R9") (pin "1") (pinfunction "1_1") (pintype "passive"))
      (node (ref "U4") (pin "22") (pinfunction "RXN_22") (pintype "bidirectional"))
    )
    (net (code "58") (name "RX_P") (class "Default")
      (node (ref "J1") (pin "3") (pinfunction "RD+_3") (pintype "bidirectional"))
      (node (ref "R8") (pin "1") (pinfunction "1_1") (pintype "passive"))
      (node (ref "U4") (pin "23") (pinfunction "RXP_23") (pintype "bidirectional"))
    )
    (net (code "59") (name "SCK") (class "Default")
      (node (ref "LCD1") (pin "9") (pinfunction "SCK_9") (pintype "bidirectional"))
      (node (ref "U2") (pin "9") (pinfunction "IO33_9") (pintype "bidirectional"))
      (node (ref "U5") (pin "12") (pinfunction "SCK_12") (pintype "bidirectional"))
      (node (ref "U58") (pin "16") (pinfunction "DCLK_16") (pintype "bidirectional"))
    )
    (net (code "60") (name "SPEED_LED") (class "Default")
      (node (ref "J1") (pin "12") (pinfunction "YLED+_12") (pintype "bidirectional"))
      (node (ref "R4") (pin "2") (pinfunction "2_2") (pintype "passive"))
      (node (ref "U4") (pin "2") (pinfunction "LED2_2") (pintype "bidirectional"))
    )
    (net (code "61") (name "TX_N") (class "Default")
      (node (ref "J1") (pin "2") (pinfunction "TD-_2") (pintype "bidirectional"))
      (node (ref "R7") (pin "1") (pinfunction "1_1") (pintype "passive"))
      (node (ref "U4") (pin "20") (pinfunction "TXN_20") (pintype "bidirectional"))
    )
    (net (code "62") (name "TX_P") (class "Default")
      (node (ref "J1") (pin "1") (pinfunction "TD+_1") (pintype "bidirectional"))
      (node (ref "R6") (pin "1") (pinfunction "1_1") (pintype "passive"))
      (node (ref "U4") (pin "21") (pinfunction "TXP_21") (pintype "bidirectional"))
    )
    (net (code "63") (name "USB_DN") (class "Default")
      (node (ref "R14") (pin "2") (pinfunction "2_2") (pintype "passive"))
      (node (ref "U1") (pin "6") (pinfunction "UD-_6") (pintype "bidirectional"))
    )
    (net (code "64") (name "USB_DP") (class "Default")
      (node (ref "R15") (pin "2") (pinfunction "2_2") (pintype "passive"))
      (node (ref "U1") (pin "5") (pinfunction "UD+_5") (pintype "bidirectional"))
    )
    (net (code "65") (name "VDDRC") (class "Default")
      (node (ref "C5") (pin "2") (pinfunction "2_2") (pintype "passive"))
      (node (ref "C6") (pin "2") (pinfunction "2_2") (pintype "passive"))
      (node (ref "U4") (pin "6") (pinfunction "VDDCR_6") (pintype "bidirectional"))
    )
    (net (code "66") (name "XL") (class "Default")
      (node (ref "LCD1") (pin "T2") (pinfunction "XL_T2") (pintype "bidirectional"))
      (node (ref "U58") (pin "4") (pinfunction "XN_4") (pintype "bidirectional"))
    )
    (net (code "67") (name "XP_CS") (class "Default")
      (node (ref "U2") (pin "23") (pinfunction "IO15_23") (pintype "bidirectional"))
      (node (ref "U58") (pin "15") (pinfunction "CS_15") (pintype "bidirectional"))
    )
    (net (code "68") (name "XR") (class "Default")
      (node (ref "LCD1") (pin "T4") (pinfunction "XR_T4") (pintype "bidirectional"))
      (node (ref "U58") (pin "2") (pinfunction "XP_2") (pintype "bidirectional"))
    )
    (net (code "69") (name "YD") (class "Default")
      (node (ref "LCD1") (pin "T3") (pinfunction "YD_T3") (pintype "bidirectional"))
      (node (ref "U58") (pin "3") (pinfunction "YP_3") (pintype "bidirectional"))
    )
    (net (code "70") (name "YU") (class "Default")
      (node (ref "LCD1") (pin "T1") (pinfunction "YU_T1") (pintype "bidirectional"))
      (node (ref "U58") (pin "5") (pinfunction "YN_5") (pintype "bidirectional"))
    )
    (net (code "71") (name "unconnected-(J3-PadA8)") (class "Default")
      (node (ref "J3") (pin "A8") (pinfunction "A8_A8") (pintype "bidirectional"))
    )
    (net (code "72") (name "unconnected-(J3-PadB8)") (class "Default")
      (node (ref "J3") (pin "B8") (pinfunction "B8_B8") (pintype "bidirectional"))
    )
    (net (code "73") (name "unconnected-(U1-CTS#-Pad9)") (class "Default")
      (node (ref "U1") (pin "9") (pinfunction "CTS#_9") (pintype "bidirectional"))
    )
    (net (code "74") (name "unconnected-(U1-DCD#-Pad12)") (class "Default")
      (node (ref "U1") (pin "12") (pinfunction "DCD#_12") (pintype "bidirectional"))
    )
    (net (code "75") (name "unconnected-(U1-DSR#-Pad10)") (class "Default")
      (node (ref "U1") (pin "10") (pinfunction "DSR#_10") (pintype "bidirectional"))
    )
    (net (code "76") (name "unconnected-(U1-DTR#-Pad13)") (class "Default")
      (node (ref "U1") (pin "13") (pinfunction "DTR#_13") (pintype "bidirectional"))
    )
    (net (code "77") (name "unconnected-(U1-RI#-Pad11)") (class "Default")
      (node (ref "U1") (pin "11") (pinfunction "RI#_11") (pintype "bidirectional"))
    )
    (net (code "78") (name "unconnected-(U1-RS232-Pad15)") (class "Default")
      (node (ref "U1") (pin "15") (pinfunction "RS232_15") (pintype "bidirectional"))
    )
    (net (code "79") (name "unconnected-(U1-RTS#-Pad14)") (class "Default")
      (node (ref "U1") (pin "14") (pinfunction "RTS#_14") (pintype "bidirectional"))
    )
    (net (code "80") (name "unconnected-(U1-XI-Pad7)") (class "Default")
      (node (ref "U1") (pin "7") (pinfunction "XI_7") (pintype "bidirectional"))
    )
    (net (code "81") (name "unconnected-(U1-XO-Pad8)") (class "Default")
      (node (ref "U1") (pin "8") (pinfunction "XO_8") (pintype "bidirectional"))
    )
    (net (code "82") (name "unconnected-(U2-NC-Pad32)") (class "Default")
      (node (ref "U2") (pin "32") (pinfunction "NC_32") (pintype "bidirectional"))
    )
    (net (code "83") (name "unconnected-(U2-NC1-Pad17)") (class "Default")
      (node (ref "U2") (pin "17") (pinfunction "NC1_17") (pintype "bidirectional"))
    )
    (net (code "84") (name "unconnected-(U2-NC2-Pad18)") (class "Default")
      (node (ref "U2") (pin "18") (pinfunction "NC2_18") (pintype "bidirectional"))
    )
    (net (code "85") (name "unconnected-(U2-NC3-Pad19)") (class "Default")
      (node (ref "U2") (pin "19") (pinfunction "NC3_19") (pintype "bidirectional"))
    )
    (net (code "86") (name "unconnected-(U2-NC4-Pad20)") (class "Default")
      (node (ref "U2") (pin "20") (pinfunction "NC4_20") (pintype "bidirectional"))
    )
    (net (code "87") (name "unconnected-(U2-NC5-Pad21)") (class "Default")
      (node (ref "U2") (pin "21") (pinfunction "NC5_21") (pintype "bidirectional"))
    )
    (net (code "88") (name "unconnected-(U2-NC6-Pad22)") (class "Default")
      (node (ref "U2") (pin "22") (pinfunction "NC6_22") (pintype "bidirectional"))
    )
    (net (code "89") (name "unconnected-(U2-SEN_VP-Pad4)") (class "Default")
      (node (ref "U2") (pin "4") (pinfunction "SEN_VP_4") (pintype "bidirectional"))
    )
    (net (code "90") (name "unconnected-(U4-RXER-Pad10)") (class "Default")
      (node (ref "U4") (pin "10") (pinfunction "RXER_10") (pintype "bidirectional"))
    )
    (net (code "91") (name "unconnected-(U4-XTAL2-Pad4)") (class "Default")
      (node (ref "U4") (pin "4") (pinfunction "XTAL2_4") (pintype "bidirectional"))
    )
    (net (code "92") (name "unconnected-(U5-DIO2-Pad7)") (class "Default")
      (node (ref "U5") (pin "7") (pinfunction "DIO2_7") (pintype "bidirectional"))
    )
    (net (code "93") (name "unconnected-(U5-DIO3-Pad8)") (class "Default")
      (node (ref "U5") (pin "8") (pinfunction "DIO3_8") (pintype "bidirectional"))
    )
    (net (code "94") (name "unconnected-(U5-RXEN-Pad11)") (class "Default")
      (node (ref "U5") (pin "11") (pinfunction "RXEN_11") (pintype "bidirectional"))
    )
    (net (code "95") (name "unconnected-(U5-TXEN-Pad5)") (class "Default")
      (node (ref "U5") (pin "5") (pinfunction "TXEN_5") (pintype "bidirectional"))
    )
    (net (code "96") (name "unconnected-(U58-BUESY-Pad13)") (class "Default")
      (node (ref "U58") (pin "13") (pinfunction "BUESY_13") (pintype "bidirectional"))
    )
    (net (code "97") (name "unconnected-(U58-IN-Pad8)") (class "Default")
      (node (ref "U58") (pin "8") (pinfunction "IN_8") (pintype "bidirectional"))
    )
    (net (code "98") (name "unconnected-(U58-VBAT-Pad7)") (class "Default")
      (node (ref "U58") (pin "7") (pinfunction "VBAT_7") (pintype "bidirectional"))
    )
  )
)
